# Arduino__Connectors.net
KiCad netlist of a schematic drawn in Altium Designer
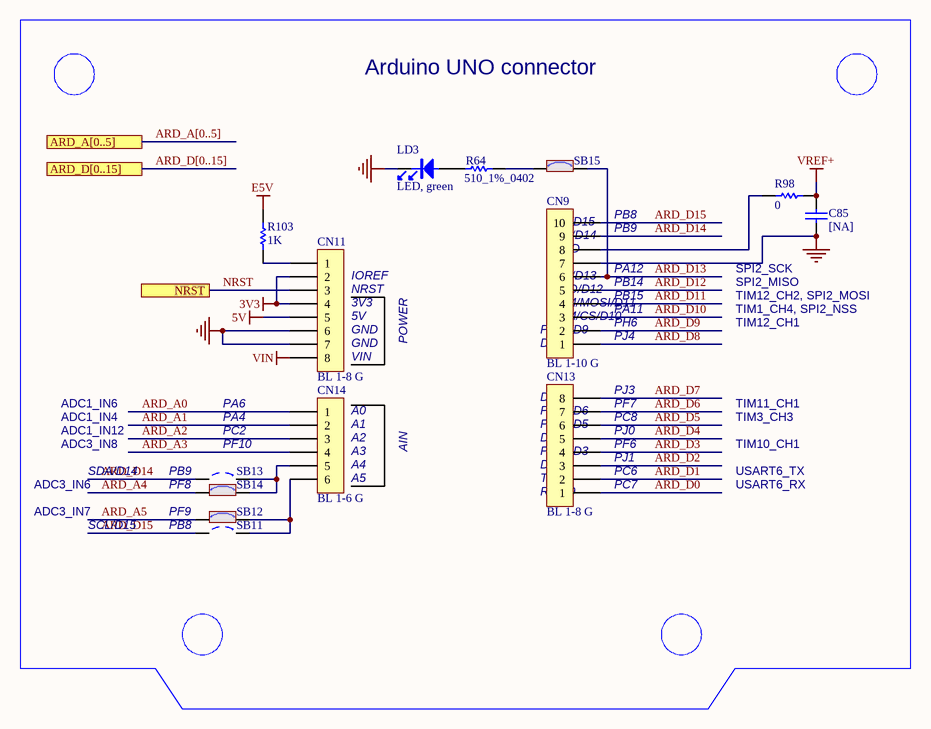
[diagram p0: Arduino_ Connectors.SchDoc]

(export (version "E")
  (design (tool "Eeschema 10.0.6"))
  (components
    (comp (ref "C85")
      (value "[NA]")
      (footprint "0402C")
      (description "Capacitor,NA,0402")
      (libsource (lib "MCD_TOOLS") (part "Cap_NA_0402"))
    )
    (comp (ref "CN9")
      (value "BL 1-10 G")
      (footprint "HDR_1X10_2R54_W")
      (description "Header, 10-Pin, Single row, female, THT, 2.54")
      (libsource (lib "MCD_TOOLS_CONNECTOR") (part "Header 10X1_Female_THT"))
    )
    (comp (ref "CN11")
      (value "BL 1-8 G")
      (footprint "HDR_1X8_2R54_W")
      (description "Header, 8-Pins, Single row, female, THT, 2.54")
      (libsource (lib "MCD_TOOLS_CONNECTOR") (part "Header 8X1_Female_THT"))
    )
    (comp (ref "CN13")
      (value "BL 1-8 G")
      (footprint "HDR_1X8_2R54_W")
      (description "Header, 8-Pins, Single row, female, THT, 2.54")
      (libsource (lib "") (part "Header 8X1_Female_THT_1"))
    )
    (comp (ref "CN14")
      (value "BL 1-6 G")
      (footprint "HDR_1X6_2R54_W")
      (description "Header, 6-Pins, Single row, female THT, 2.54")
      (libsource (lib "MCD_TOOLS_CONNECTOR") (part "Header 6X1_Female_THT"))
    )
    (comp (ref "LD3")
      (value "LED, green")
      (footprint "0603D")
      (description "LED, green, 0603")
      (libsource (lib "MCD_TOOLS") (part "LED_green"))
    )
    (comp (ref "R64")
      (value "510_1%_0402")
      (footprint "0402R")
      (description "Resistor,510,0402,1%,YAGEO")
      (libsource (lib "MCD_TOOLS") (part "Res_510_1%_0402"))
    )
    (comp (ref "R98")
      (value "0")
      (footprint "0402R")
      (description "Resistor,0,0402,5%,YAGEO")
      (libsource (lib "MCD_TOOLS") (part "Res_0_5%_0402"))
    )
    (comp (ref "R103")
      (value "1K")
      (footprint "0402R")
      (description "Resistor,1K,0402,1%,YAGEO")
      (libsource (lib "MCD_TOOLS_RESISTOR") (part "Res_1K_1%_0402"))
    )
    (comp (ref "SB11")
      (value "Solder Bridge OFF")
      (footprint "JP2_SMD")
      (libsource (lib "MCD_TOOLS") (part "SB_OFF"))
    )
    (comp (ref "SB12")
      (value "Solder Bridge ON")
      (footprint "JP2_SMD")
      (libsource (lib "MCD_TOOLS") (part "SB_ON"))
    )
    (comp (ref "SB13")
      (value "Solder Bridge OFF")
      (footprint "JP2_SMD")
      (libsource (lib "MCD_TOOLS") (part "SB_OFF"))
    )
    (comp (ref "SB14")
      (value "Solder Bridge ON")
      (footprint "JP2_SMD")
      (libsource (lib "MCD_TOOLS") (part "SB_ON"))
    )
    (comp (ref "SB15")
      (value "Solder Bridge ON")
      (footprint "JP2_SMD")
      (libsource (lib "MCD_TOOLS") (part "SB_ON"))
    )
  )
  (nets
    (net (code "1") (name "/ARD_A0") (class "Default")
      (node (ref "CN14") (pin "1") (pinfunction "1_1") (pintype "passive"))
    )
    (net (code "2") (name "/ARD_A1") (class "Default")
      (node (ref "CN14") (pin "2") (pinfunction "2_2") (pintype "passive"))
    )
    (net (code "3") (name "/ARD_A2") (class "Default")
      (node (ref "CN14") (pin "3") (pinfunction "3_3") (pintype "passive"))
    )
    (net (code "4") (name "/ARD_A3") (class "Default")
      (node (ref "CN14") (pin "4") (pinfunction "4_4") (pintype "passive"))
    )
    (net (code "5") (name "/ARD_A4") (class "Default")
      (node (ref "SB14") (pin "1") (pinfunction "1_1") (pintype "passive"))
    )
    (net (code "6") (name "/ARD_A5") (class "Default")
      (node (ref "SB12") (pin "1") (pinfunction "1_1") (pintype "passive"))
    )
    (net (code "8") (name "/ARD_D0") (class "Default")
      (node (ref "CN13") (pin "1") (pinfunction "1_1") (pintype "passive"))
    )
    (net (code "9") (name "/ARD_D1") (class "Default")
      (node (ref "CN13") (pin "2") (pinfunction "2_2") (pintype "passive"))
    )
    (net (code "10") (name "/ARD_D2") (class "Default")
      (node (ref "CN13") (pin "3") (pinfunction "3_3") (pintype "passive"))
    )
    (net (code "11") (name "/ARD_D3") (class "Default")
      (node (ref "CN13") (pin "4") (pinfunction "4_4") (pintype "passive"))
    )
    (net (code "12") (name "/ARD_D4") (class "Default")
      (node (ref "CN13") (pin "5") (pinfunction "5_5") (pintype "passive"))
    )
    (net (code "13") (name "/ARD_D5") (class "Default")
      (node (ref "CN13") (pin "6") (pinfunction "6_6") (pintype "passive"))
    )
    (net (code "14") (name "/ARD_D6") (class "Default")
      (node (ref "CN13") (pin "7") (pinfunction "7_7") (pintype "passive"))
    )
    (net (code "15") (name "/ARD_D7") (class "Default")
      (node (ref "CN13") (pin "8") (pinfunction "8_8") (pintype "passive"))
    )
    (net (code "16") (name "/ARD_D8") (class "Default")
      (node (ref "CN9") (pin "1") (pinfunction "1_1") (pintype "passive"))
    )
    (net (code "17") (name "/ARD_D9") (class "Default")
      (node (ref "CN9") (pin "2") (pinfunction "2_2") (pintype "passive"))
    )
    (net (code "18") (name "/ARD_D10") (class "Default")
      (node (ref "CN9") (pin "3") (pinfunction "3_3") (pintype "passive"))
    )
    (net (code "19") (name "/ARD_D11") (class "Default")
      (node (ref "CN9") (pin "4") (pinfunction "4_4") (pintype "passive"))
    )
    (net (code "20") (name "/ARD_D12") (class "Default")
      (node (ref "CN9") (pin "5") (pinfunction "5_5") (pintype "passive"))
    )
    (net (code "21") (name "/ARD_D13") (class "Default")
      (node (ref "CN9") (pin "6") (pinfunction "6_6") (pintype "passive"))
      (node (ref "SB15") (pin "2") (pinfunction "2_2") (pintype "passive"))
    )
    (net (code "22") (name "/ARD_D14") (class "Default")
      (node (ref "CN9") (pin "9") (pinfunction "9_9") (pintype "passive"))
      (node (ref "SB13") (pin "1") (pinfunction "1_1") (pintype "passive"))
    )
    (net (code "23") (name "/ARD_D15") (class "Default")
      (node (ref "CN9") (pin "10") (pinfunction "10_10") (pintype "passive"))
      (node (ref "SB11") (pin "1") (pinfunction "1_1") (pintype "passive"))
    )
    (net (code "25") (name "/NRST") (class "Default")
      (node (ref "CN11") (pin "3") (pinfunction "3_3") (pintype "passive"))
    )
    (net (code "26") (name "3V3") (class "Default")
      (node (ref "CN11") (pin "2") (pinfunction "2_2") (pintype "passive"))
      (node (ref "CN11") (pin "4") (pinfunction "4_4") (pintype "passive"))
    )
    (net (code "27") (name "5V") (class "Default")
      (node (ref "CN11") (pin "5") (pinfunction "5_5") (pintype "passive"))
    )
    (net (code "28") (name "E5V") (class "Default")
      (node (ref "R103") (pin "2") (pinfunction "2_2") (pintype "passive"))
    )
    (net (code "29") (name "GND") (class "Default")
      (node (ref "C85") (pin "1") (pinfunction "1_1") (pintype "passive"))
      (node (ref "CN11") (pin "6") (pinfunction "6_6") (pintype "passive"))
      (node (ref "CN11") (pin "7") (pinfunction "7_7") (pintype "passive"))
      (node (ref "CN9") (pin "7") (pinfunction "7_7") (pintype "passive"))
      (node (ref "LD3") (pin "2") (pintype "passive"))
    )
    (net (code "30") (name "Net-(CN9-Pad8)") (class "Default")
      (node (ref "CN9") (pin "8") (pinfunction "8_8") (pintype "passive"))
      (node (ref "R98") (pin "1") (pinfunction "1_1") (pintype "passive"))
    )
    (net (code "31") (name "Net-(CN11-Pad1)") (class "Default")
      (node (ref "CN11") (pin "1") (pinfunction "1_1") (pintype "passive"))
      (node (ref "R103") (pin "1") (pinfunction "1_1") (pintype "passive"))
    )
    (net (code "32") (name "Net-(CN14-Pad5)") (class "Default")
      (node (ref "CN14") (pin "5") (pinfunction "5_5") (pintype "passive"))
      (node (ref "SB13") (pin "2") (pinfunction "2_2") (pintype "passive"))
      (node (ref "SB14") (pin "2") (pinfunction "2_2") (pintype "passive"))
    )
    (net (code "33") (name "Net-(CN14-Pad6)") (class "Default")
      (node (ref "CN14") (pin "6") (pinfunction "6_6") (pintype "passive"))
      (node (ref "SB11") (pin "2") (pinfunction "2_2") (pintype "passive"))
      (node (ref "SB12") (pin "2") (pinfunction "2_2") (pintype "passive"))
    )
    (net (code "34") (name "Net-(LD3-Pad1)") (class "Default")
      (node (ref "LD3") (pin "1") (pintype "passive"))
      (node (ref "R64") (pin "1") (pinfunction "1_1") (pintype "passive"))
    )
    (net (code "35") (name "Net-(R64-Pad2)") (class "Default")
      (node (ref "R64") (pin "2") (pinfunction "2_2") (pintype "passive"))
      (node (ref "SB15") (pin "1") (pinfunction "1_1") (pintype "passive"))
    )
    (net (code "36") (name "VIN") (class "Default")
      (node (ref "CN11") (pin "8") (pinfunction "8_8") (pintype "passive"))
    )
    (net (code "37") (name "VREF+") (class "Default")
      (node (ref "C85") (pin "2") (pinfunction "2_2") (pintype "passive"))
      (node (ref "R98") (pin "2") (pinfunction "2_2") (pintype "passive"))
    )
  )
)
